# squematics.net
KiCad netlist of a schematic drawn in EAGLE
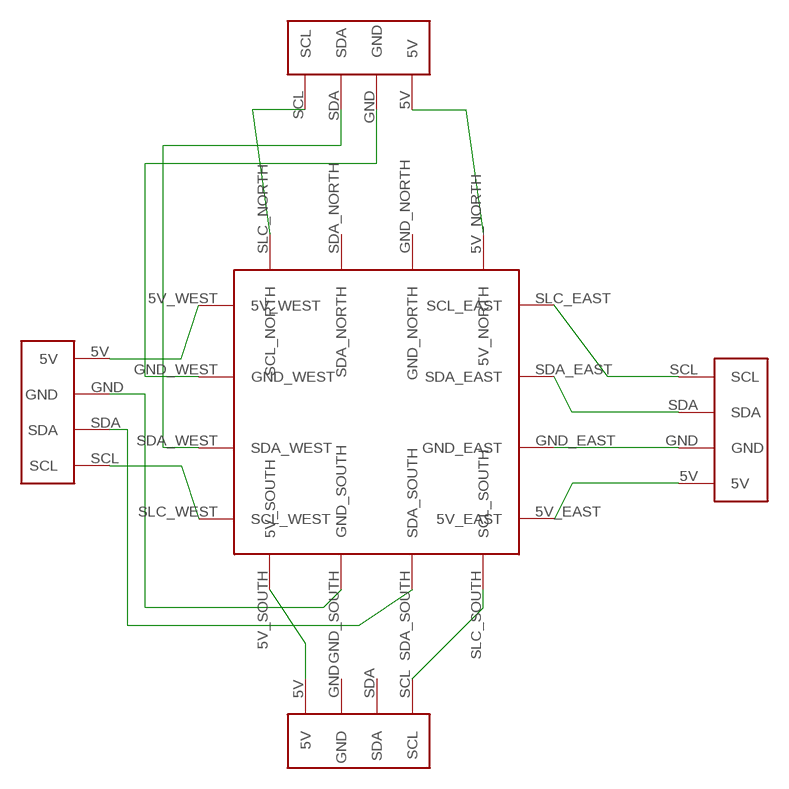
[diagram p0: schematic, sheet 1]

(export (version "E")
  (design (tool "Eeschema 10.0.6"))
  (components
    (comp (ref "EAST")
      (value "FOUR_SIDE_PINS")
      (footprint "eagle-import:FOUR_SIDE_PINS")
      (libsource (lib "eagle-import") (part "FOUR_SIDE_PINS"))
    )
    (comp (ref "NORTH")
      (value "FOUR_SIDE_PINS")
      (footprint "eagle-import:FOUR_SIDE_PINS")
      (libsource (lib "eagle-import") (part "FOUR_SIDE_PINS"))
    )
    (comp (ref "U$1")
      (value "CONNECTORS_PIN_DEVICE")
      (footprint "eagle-import:CONNECTORS_PIN")
      (libsource (lib "eagle-import") (part "CONNECTORS_PIN_DEVICE"))
    )
    (comp (ref "U$2")
      (value "FOUR_SIDE_PINS")
      (footprint "eagle-import:FOUR_SIDE_PINS")
      (libsource (lib "eagle-import") (part "FOUR_SIDE_PINS"))
    )
    (comp (ref "U$3")
      (value "FOUR_SIDE_PINS")
      (footprint "eagle-import:FOUR_SIDE_PINS")
      (libsource (lib "eagle-import") (part "FOUR_SIDE_PINS"))
    )
  )
  (nets
    (net (code "1") (name "Net-(EAST-Pad5V)") (class "Default")
      (node (ref "EAST") (pin "5V") (pinfunction "5V_5V") (pintype "bidirectional"))
      (node (ref "U$1") (pin "5V_EAST") (pinfunction "5V_EAST_5V_EAST") (pintype "bidirectional"))
    )
    (net (code "2") (name "Net-(EAST-PadGND)") (class "Default")
      (node (ref "EAST") (pin "GND") (pinfunction "GND_GND") (pintype "bidirectional"))
      (node (ref "U$1") (pin "GND_EAST") (pinfunction "GND_EAST_GND_EAST") (pintype "bidirectional"))
    )
    (net (code "3") (name "Net-(EAST-PadSDA)") (class "Default")
      (node (ref "EAST") (pin "SDA") (pinfunction "SDA_SDA") (pintype "bidirectional"))
      (node (ref "U$1") (pin "SDA_EAST") (pinfunction "SDA_EAST_SDA_EAST") (pintype "bidirectional"))
    )
    (net (code "4") (name "Net-(NORTH-Pad5V)") (class "Default")
      (node (ref "NORTH") (pin "5V") (pinfunction "5V_5V") (pintype "bidirectional"))
      (node (ref "U$1") (pin "5V_NORTH") (pinfunction "5V_NORTH_5V_NORTH") (pintype "bidirectional"))
    )
    (net (code "5") (name "Net-(NORTH-PadGND)") (class "Default")
      (node (ref "NORTH") (pin "GND") (pinfunction "GND_GND") (pintype "bidirectional"))
      (node (ref "U$1") (pin "GND_WEST") (pinfunction "GND_WEST_GND_WEST") (pintype "bidirectional"))
    )
    (net (code "6") (name "Net-(NORTH-PadSDA)") (class "Default")
      (node (ref "NORTH") (pin "SDA") (pinfunction "SDA_SDA") (pintype "bidirectional"))
      (node (ref "U$1") (pin "SDA_WEST") (pinfunction "SDA_WEST_SDA_WEST") (pintype "bidirectional"))
    )
    (net (code "7") (name "Net-(U$1-Pad5V_SOUTH)") (class "Default")
      (node (ref "U$1") (pin "5V_SOUTH") (pinfunction "5V_SOUTH_5V_SOUTH") (pintype "bidirectional"))
      (node (ref "U$3") (pin "5V") (pinfunction "5V_5V") (pintype "bidirectional"))
    )
    (net (code "8") (name "Net-(U$1-Pad5V_WEST)") (class "Default")
      (node (ref "U$1") (pin "5V_WEST") (pinfunction "5V_WEST_5V_WEST") (pintype "bidirectional"))
      (node (ref "U$2") (pin "5V") (pinfunction "5V_5V") (pintype "bidirectional"))
    )
    (net (code "9") (name "Net-(U$1-PadGND_SOUTH)") (class "Default")
      (node (ref "U$1") (pin "GND_SOUTH") (pinfunction "GND_SOUTH_GND_SOUTH") (pintype "bidirectional"))
      (node (ref "U$2") (pin "GND") (pinfunction "GND_GND") (pintype "bidirectional"))
    )
    (net (code "10") (name "Net-(U$1-PadSDA_SOUTH)") (class "Default")
      (node (ref "U$1") (pin "SDA_SOUTH") (pinfunction "SDA_SOUTH_SDA_SOUTH") (pintype "bidirectional"))
      (node (ref "U$2") (pin "SDA") (pinfunction "SDA_SDA") (pintype "bidirectional"))
    )
    (net (code "11") (name "Net-(U$1-SCL_EAST)") (class "Default")
      (node (ref "EAST") (pin "SCL") (pinfunction "SCL_SCL") (pintype "bidirectional"))
      (node (ref "U$1") (pin "SLC_EAST") (pinfunction "SCL_EAST_SLC_EAST") (pintype "bidirectional"))
    )
    (net (code "12") (name "Net-(U$1-SCL_NORTH)") (class "Default")
      (node (ref "NORTH") (pin "SCL") (pinfunction "SCL_SCL") (pintype "bidirectional"))
      (node (ref "U$1") (pin "SLC_NORTH") (pinfunction "SCL_NORTH_SLC_NORTH") (pintype "bidirectional"))
    )
    (net (code "13") (name "Net-(U$1-SCL_SOUTH)") (class "Default")
      (node (ref "U$1") (pin "SLC_SOUTH") (pinfunction "SCL_SOUTH_SLC_SOUTH") (pintype "bidirectional"))
      (node (ref "U$3") (pin "SCL") (pinfunction "SCL_SCL") (pintype "bidirectional"))
    )
    (net (code "14") (name "Net-(U$1-SCL_WEST)") (class "Default")
      (node (ref "U$1") (pin "SLC_WEST") (pinfunction "SCL_WEST_SLC_WEST") (pintype "bidirectional"))
      (node (ref "U$2") (pin "SCL") (pinfunction "SCL_SCL") (pintype "bidirectional"))
    )
    (net (code "15") (name "unconnected-(U$1-PadGND_NORTH)") (class "Default")
      (node (ref "U$1") (pin "GND_NORTH") (pinfunction "GND_NORTH_GND_NORTH") (pintype "bidirectional"))
    )
    (net (code "16") (name "unconnected-(U$1-PadSDA_NORTH)") (class "Default")
      (node (ref "U$1") (pin "SDA_NORTH") (pinfunction "SDA_NORTH_SDA_NORTH") (pintype "bidirectional"))
    )
    (net (code "17") (name "unconnected-(U$3-PadGND)") (class "Default")
      (node (ref "U$3") (pin "GND") (pinfunction "GND_GND") (pintype "bidirectional"))
    )
    (net (code "18") (name "unconnected-(U$3-PadSDA)") (class "Default")
      (node (ref "U$3") (pin "SDA") (pinfunction "SDA_SDA") (pintype "bidirectional"))
    )
  )
)
